# hud_v300_PWR.net
KiCad netlist of a schematic drawn in Altium Designer
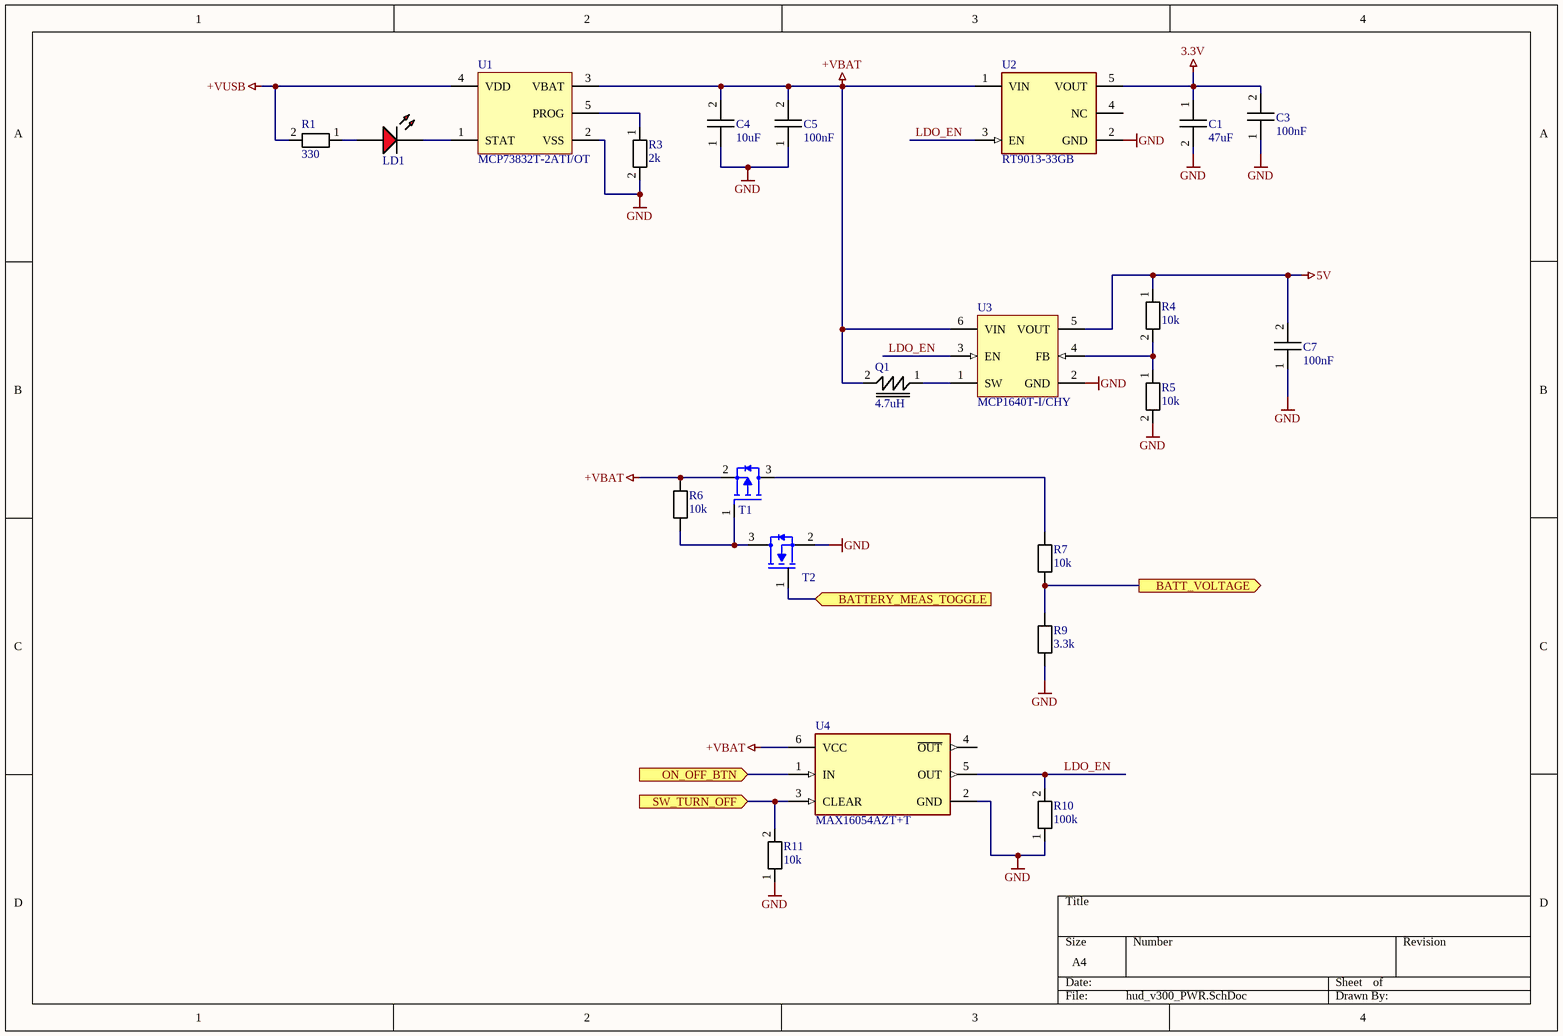
[diagram p0: hud_v300_PWR.SchDoc]

(export (version "E")
  (design (tool "Eeschema 10.0.6"))
  (components
    (comp (ref "C1") (value "47uF") (footprint "0805_C") (libsource (lib "Schlib1") (part "CAPACITOR")))
    (comp (ref "C3") (value "100nF") (footprint "0805_C") (libsource (lib "Schlib1") (part "CAPACITOR")))
    (comp (ref "C4") (value "10uF") (footprint "1210_C") (libsource (lib "Schlib1") (part "CAPACITOR")))
    (comp (ref "C5") (value "100nF") (footprint "0805_C") (libsource (lib "Schlib1") (part "CAPACITOR")))
    (comp (ref "C7") (value "100nF") (footprint "0805_C") (libsource (lib "Schlib1") (part "CAPACITOR")))
    (comp (ref "LD1")
      (value "LED_RED")
      (footprint "LED_SMD_90DEG_RED")
      (libsource (lib "Schlib1") (part "LED_RED"))
    )
    (comp (ref "Q1") (value "4.7uH") (footprint "1210") (libsource (lib "Schlib1") (part "COIL")))
    (comp (ref "R1") (value "330") (footprint "0805") (libsource (lib "Schlib1") (part "RESISTOR")))
    (comp (ref "R3") (value "2k") (footprint "0805") (libsource (lib "Schlib1") (part "RESISTOR")))
    (comp (ref "R4") (value "10k") (footprint "0805") (libsource (lib "Schlib1") (part "RESISTOR")))
    (comp (ref "R5") (value "10k") (footprint "0805") (libsource (lib "Schlib1") (part "RESISTOR")))
    (comp (ref "R6") (value "10k") (footprint "0805") (libsource (lib "") (part "RESISTOR_1")))
    (comp (ref "R7") (value "10k") (footprint "0805") (libsource (lib "") (part "RESISTOR_1")))
    (comp (ref "R9") (value "3.3k") (footprint "0805") (libsource (lib "") (part "RESISTOR_1")))
    (comp (ref "R10") (value "100k") (footprint "0805") (libsource (lib "Schlib1") (part "RESISTOR")))
    (comp (ref "R11") (value "10k") (footprint "0805") (libsource (lib "Schlib1") (part "RESISTOR")))
    (comp (ref "T1")
      (value "BSS84")
      (footprint "SOT23")
      (description "P-Chanel MOSFET")
      (libsource (lib "Schlib1") (part "BSS84"))
    )
    (comp (ref "T2")
      (value "MMBF170")
      (footprint "SOT23")
      (description "N MOSFET")
      (libsource (lib "Schlib1") (part "MMBF170"))
    )
    (comp (ref "U1")
      (value "MCP73832T-2ATI/OT")
      (footprint "SOT23-5")
      (libsource (lib "pwr_mgt") (part "MCP73832T-2ATI/OT"))
    )
    (comp (ref "U2")
      (value "RT9013-33GB")
      (footprint "SOT23-5")
      (description "500mA, Low Dropout, Low Noise Ultra-Fast Without\r\nBypass Capacitor CMOS LDO Regulator")
      (libsource (lib "pwr_mgt") (part "RT9013-33GB"))
    )
    (comp (ref "U3")
      (value "MCP1640T-I/CHY")
      (footprint "SOT23-6")
      (libsource (lib "pwr_mgt") (part "MCP1640T-I/CHY"))
    )
    (comp (ref "U4")
      (value "MAX16054AZT+T")
      (footprint "FP-Z6-1-IPC_A")
      (description "IC INTFACE SPECIALIZED TSOT23-6")
      (libsource (lib "Altium Content Vault") (part "cdb3212196b4b4bbabc319418359328"))
    )
  )
  (nets
    (net (code "1") (name "+VBAT") (class "Default")
      (node (ref "C4") (pin "2") (pinfunction "2_2") (pintype "passive"))
      (node (ref "C5") (pin "2") (pinfunction "2_2") (pintype "passive"))
      (node (ref "Q1") (pin "2") (pinfunction "2_2") (pintype "passive"))
      (node (ref "R6") (pin "2") (pinfunction "1_2") (pintype "passive"))
      (node (ref "T1") (pin "2") (pinfunction "S_2") (pintype "passive"))
      (node (ref "U1") (pin "3") (pinfunction "VBAT_3") (pintype "power_in"))
      (node (ref "U2") (pin "1") (pinfunction "VIN_1") (pintype "power_in"))
      (node (ref "U3") (pin "6") (pinfunction "VIN_6") (pintype "power_in"))
      (node (ref "U4") (pin "6") (pinfunction "VCC_6") (pintype "power_in"))
    )
    (net (code "2") (name "+VUSB") (class "Default")
      (node (ref "R1") (pin "2") (pinfunction "1_2") (pintype "passive"))
      (node (ref "U1") (pin "4") (pinfunction "VDD_4") (pintype "power_in"))
    )
    (net (code "3") (name "/BATTERY_MEAS_TOGGLE") (class "Default")
      (node (ref "T2") (pin "1") (pinfunction "Gate_1") (pintype "passive"))
    )
    (net (code "4") (name "/BATT_VOLTAGE") (class "Default")
      (node (ref "R7") (pin "1") (pinfunction "0_1") (pintype "passive"))
      (node (ref "R9") (pin "2") (pinfunction "1_2") (pintype "passive"))
    )
    (net (code "5") (name "/LDO_EN") (class "Default")
      (node (ref "R10") (pin "2") (pinfunction "1_2") (pintype "passive"))
      (node (ref "U2") (pin "3") (pinfunction "EN_3") (pintype "input"))
      (node (ref "U3") (pin "3") (pinfunction "EN_3") (pintype "input"))
      (node (ref "U4") (pin "5") (pinfunction "OUT_5") (pintype "output"))
    )
    (net (code "6") (name "/ON_OFF_BTN") (class "Default")
      (node (ref "U4") (pin "1") (pinfunction "IN_1") (pintype "input"))
    )
    (net (code "7") (name "/SW_TURN_OFF") (class "Default")
      (node (ref "R11") (pin "2") (pinfunction "1_2") (pintype "passive"))
      (node (ref "U4") (pin "3") (pinfunction "CLEAR_3") (pintype "input"))
    )
    (net (code "8") (name "3.3V") (class "Default")
      (node (ref "C1") (pin "1") (pinfunction "1_1") (pintype "passive"))
      (node (ref "C3") (pin "2") (pinfunction "2_2") (pintype "passive"))
      (node (ref "U2") (pin "5") (pinfunction "VOUT_5") (pintype "power_in"))
    )
    (net (code "9") (name "5V") (class "Default")
      (node (ref "C7") (pin "2") (pinfunction "2_2") (pintype "passive"))
      (node (ref "R4") (pin "1") (pinfunction "0_1") (pintype "passive"))
      (node (ref "U3") (pin "5") (pinfunction "VOUT_5") (pintype "power_in"))
    )
    (net (code "10") (name "GND") (class "Default")
      (node (ref "C1") (pin "2") (pinfunction "2_2") (pintype "passive"))
      (node (ref "C3") (pin "1") (pinfunction "1_1") (pintype "passive"))
      (node (ref "C4") (pin "1") (pinfunction "1_1") (pintype "passive"))
      (node (ref "C5") (pin "1") (pinfunction "1_1") (pintype "passive"))
      (node (ref "C7") (pin "1") (pinfunction "1_1") (pintype "passive"))
      (node (ref "R10") (pin "1") (pinfunction "0_1") (pintype "passive"))
      (node (ref "R11") (pin "1") (pinfunction "0_1") (pintype "passive"))
      (node (ref "R3") (pin "2") (pinfunction "1_2") (pintype "passive"))
      (node (ref "R5") (pin "2") (pinfunction "1_2") (pintype "passive"))
      (node (ref "R9") (pin "1") (pinfunction "0_1") (pintype "passive"))
      (node (ref "T2") (pin "2") (pinfunction "Source_2") (pintype "passive"))
      (node (ref "U1") (pin "2") (pinfunction "VSS_2") (pintype "power_in"))
      (node (ref "U2") (pin "2") (pinfunction "GND_2") (pintype "power_in"))
      (node (ref "U3") (pin "2") (pinfunction "GND_2") (pintype "power_in"))
      (node (ref "U4") (pin "2") (pinfunction "GND_2") (pintype "power_in"))
    )
    (net (code "11") (name "Net-(R1-0)") (class "Default")
      (node (ref "LD1") (pin "A") (pinfunction "A_A") (pintype "passive"))
      (node (ref "R1") (pin "1") (pinfunction "0_1") (pintype "passive"))
    )
    (net (code "12") (name "Net-(R3-0)") (class "Default")
      (node (ref "R3") (pin "1") (pinfunction "0_1") (pintype "passive"))
      (node (ref "U1") (pin "5") (pinfunction "PROG_5") (pintype "passive"))
    )
    (net (code "13") (name "Net-(R4-1)") (class "Default")
      (node (ref "R4") (pin "2") (pinfunction "1_2") (pintype "passive"))
      (node (ref "R5") (pin "1") (pinfunction "0_1") (pintype "passive"))
      (node (ref "U3") (pin "4") (pinfunction "FB_4") (pintype "input"))
    )
    (net (code "14") (name "Net-(R6-0)") (class "Default")
      (node (ref "R6") (pin "1") (pinfunction "0_1") (pintype "passive"))
      (node (ref "T1") (pin "1") (pinfunction "G_1") (pintype "passive"))
      (node (ref "T2") (pin "3") (pinfunction "Drain_3") (pintype "passive"))
    )
    (net (code "15") (name "Net-(R7-1)") (class "Default")
      (node (ref "R7") (pin "2") (pinfunction "1_2") (pintype "passive"))
      (node (ref "T1") (pin "3") (pinfunction "D_3") (pintype "passive"))
    )
    (net (code "16") (name "Net-(U1-STAT)") (class "Default")
      (node (ref "LD1") (pin "K") (pinfunction "K_K") (pintype "passive"))
      (node (ref "U1") (pin "1") (pinfunction "STAT_1") (pintype "open_collector"))
    )
    (net (code "17") (name "Net-(U3-SW)") (class "Default")
      (node (ref "Q1") (pin "1") (pinfunction "1_1") (pintype "passive"))
      (node (ref "U3") (pin "1") (pinfunction "SW_1") (pintype "power_in"))
    )
    (net (code "18") (name "unconnected-(U2-NC-Pad4)") (class "Default")
      (node (ref "U2") (pin "4") (pinfunction "NC_4") (pintype "passive"))
    )
    (net (code "19") (name "unconnected-(U4-~{OUT}-Pad4)") (class "Default")
      (node (ref "U4") (pin "4") (pinfunction "~{OUT}_4") (pintype "output"))
    )
  )
)
